# 103091_B0.net
KiCad netlist of a schematic drawn in Altium Designer
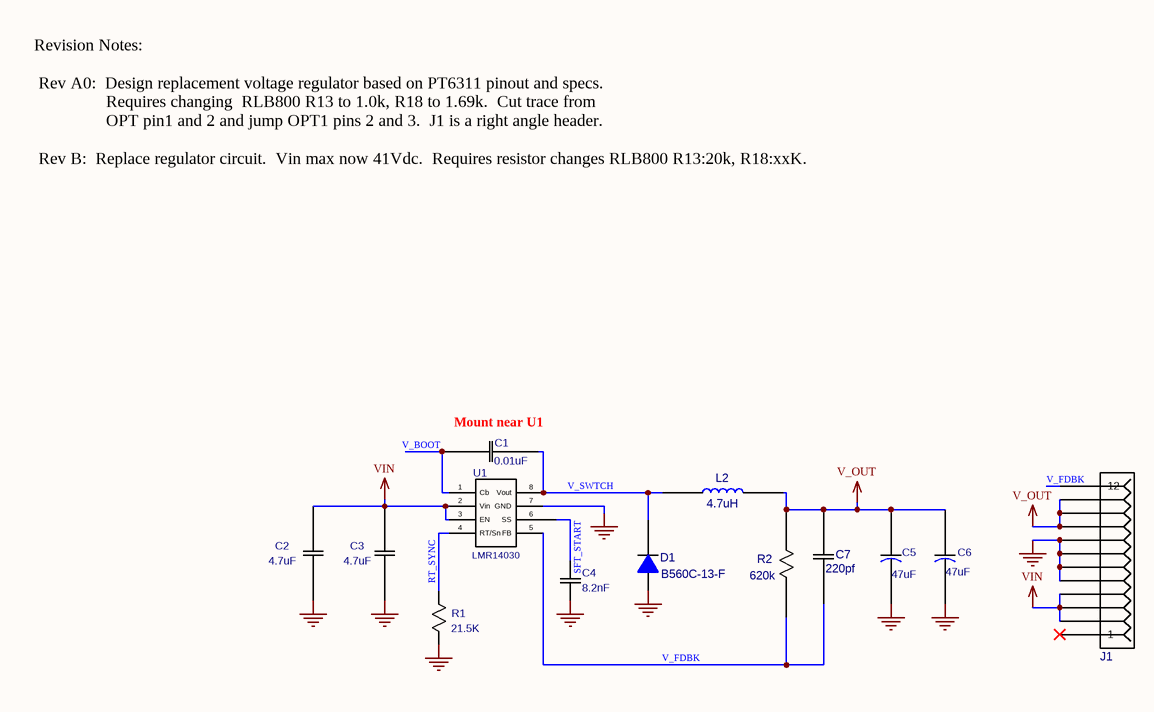
[diagram p0: 103091_B0.SchDoc]

(export (version "E")
  (design (tool "Eeschema 10.0.6"))
  (components
    (comp (ref "C1")
      (value "0.01uF")
      (footprint "CC1206")
      (description "CC1206_NP")
      (libsource (lib "*") (part "CC1206_NP"))
    )
    (comp (ref "C2")
      (value "4.7uF")
      (footprint "RES_0805")
      (description "CAP_0805")
      (libsource (lib "") (part "CAP_0805_1"))
    )
    (comp (ref "C3")
      (value "4.7uF")
      (footprint "RES_0805")
      (description "CAP_0805_VARIANT_1")
      (fields (field (name "Comment") "CAP_0805"))
      (libsource (lib "") (part "CAP_0805_1"))
    )
    (comp (ref "C4")
      (value "8.2nF")
      (footprint "RES_0805")
      (description "CAP_0805")
      (libsource (lib "*") (part "CAP_0805"))
    )
    (comp (ref "C5")
      (value "47uF")
      (footprint "CAP_SMT_10X12")
      (description "CAP_SMT_10X12")
      (libsource (lib "*") (part "CAP_SMT_10X12"))
    )
    (comp (ref "C6")
      (value "47uF")
      (footprint "CAP_SMT_10X12")
      (description "CAP_SMT_10X12")
      (libsource (lib "*") (part "CAP_SMT_10X12"))
    )
    (comp (ref "C7")
      (value "220pf")
      (footprint "RES_0805")
      (description "CAP_0805")
      (libsource (lib "") (part "CAP_0805_1"))
    )
    (comp (ref "D1")
      (value "SMC")
      (footprint "SMC")
      (fields (field (name "MFR P/N") "B560C-13-F"))
      (libsource (lib "*") (part "SMC"))
    )
    (comp (ref "J1")
      (value "HDR_100SP_12C")
      (footprint "HDR_12CR_100SP")
      (libsource (lib "*") (part "HDR_100SP_12C"))
    )
    (comp (ref "L2")
      (value "4.7uH")
      (footprint "IND_SMT_XAL50")
      (description "IND_SMT_XAL50")
      (libsource (lib "*") (part "IND_SMT_XAL50"))
    )
    (comp (ref "R1")
      (value "21.5K")
      (footprint "RES_1206")
      (description "RES_1206")
      (libsource (lib "*") (part "RES_1206"))
    )
    (comp (ref "R2")
      (value "620k")
      (footprint "RES_1206")
      (description "RES_1206")
      (libsource (lib "") (part "RES_1206_1"))
    )
    (comp (ref "U1") (value "LMR14030") (footprint "LMR14030") (libsource (lib "*") (part "LMR14030")))
  )
  (nets
    (net (code "1") (name "/RT_SYNC") (class "Default")
      (node (ref "R1") (pin "1") (pintype "passive"))
      (node (ref "U1") (pin "4") (pinfunction "RT/Sn_4") (pintype "passive"))
    )
    (net (code "2") (name "/SFT_START") (class "Default")
      (node (ref "C4") (pin "2") (pintype "passive"))
      (node (ref "U1") (pin "6") (pinfunction "SS_6") (pintype "passive"))
    )
    (net (code "3") (name "/V_BOOT") (class "Default")
      (node (ref "C1") (pin "A") (pinfunction "A_A") (pintype "passive"))
      (node (ref "U1") (pin "1") (pinfunction "Cb_1") (pintype "passive"))
    )
    (net (code "4") (name "/V_FDBK") (class "Default")
      (node (ref "C7") (pin "2") (pintype "passive"))
      (node (ref "J1") (pin "12") (pinfunction "12_12") (pintype "passive"))
      (node (ref "R2") (pin "2") (pintype "passive"))
      (node (ref "U1") (pin "5") (pinfunction "FB_5") (pintype "passive"))
    )
    (net (code "5") (name "/V_SWTCH") (class "Default")
      (node (ref "C1") (pin "B") (pinfunction "B_B") (pintype "passive"))
      (node (ref "D1") (pin "2") (pinfunction "K_2") (pintype "passive"))
      (node (ref "L2") (pin "2") (pintype "passive"))
      (node (ref "U1") (pin "8") (pinfunction "Vout_8") (pintype "power_in"))
    )
    (net (code "6") (name "GNDD") (class "Default")
      (node (ref "C2") (pin "2") (pintype "passive"))
      (node (ref "C3") (pin "2") (pintype "passive"))
      (node (ref "C4") (pin "1") (pintype "passive"))
      (node (ref "C5") (pin "1") (pintype "passive"))
      (node (ref "C6") (pin "1") (pintype "passive"))
      (node (ref "D1") (pin "1") (pinfunction "A_1") (pintype "passive"))
      (node (ref "J1") (pin "5") (pintype "passive"))
      (node (ref "J1") (pin "6") (pintype "passive"))
      (node (ref "J1") (pin "7") (pintype "passive"))
      (node (ref "J1") (pin "8") (pintype "passive"))
      (node (ref "R1") (pin "2") (pintype "passive"))
      (node (ref "U1") (pin "7") (pinfunction "GND_7") (pintype "power_in"))
    )
    (net (code "7") (name "VIN") (class "Default")
      (node (ref "C2") (pin "1") (pintype "passive"))
      (node (ref "C3") (pin "1") (pintype "passive"))
      (node (ref "J1") (pin "2") (pintype "passive"))
      (node (ref "J1") (pin "3") (pintype "passive"))
      (node (ref "J1") (pin "4") (pintype "passive"))
      (node (ref "U1") (pin "2") (pinfunction "Vin_2") (pintype "power_in"))
      (node (ref "U1") (pin "3") (pinfunction "EN_3") (pintype "passive"))
    )
    (net (code "8") (name "V_OUT") (class "Default")
      (node (ref "C5") (pin "2") (pintype "passive"))
      (node (ref "C6") (pin "2") (pintype "passive"))
      (node (ref "C7") (pin "1") (pintype "passive"))
      (node (ref "J1") (pin "10") (pintype "passive"))
      (node (ref "J1") (pin "11") (pintype "passive"))
      (node (ref "J1") (pin "9") (pintype "passive"))
      (node (ref "L2") (pin "1") (pintype "passive"))
      (node (ref "R2") (pin "1") (pintype "passive"))
    )
    (net (code "9") (name "unconnected-(J1-Pad1)") (class "Default")
      (node (ref "J1") (pin "1") (pinfunction "1_1") (pintype "passive+no_connect"))
    )
  )
)
